# Power_Supply.net
KiCad netlist of a schematic drawn in Altium Designer
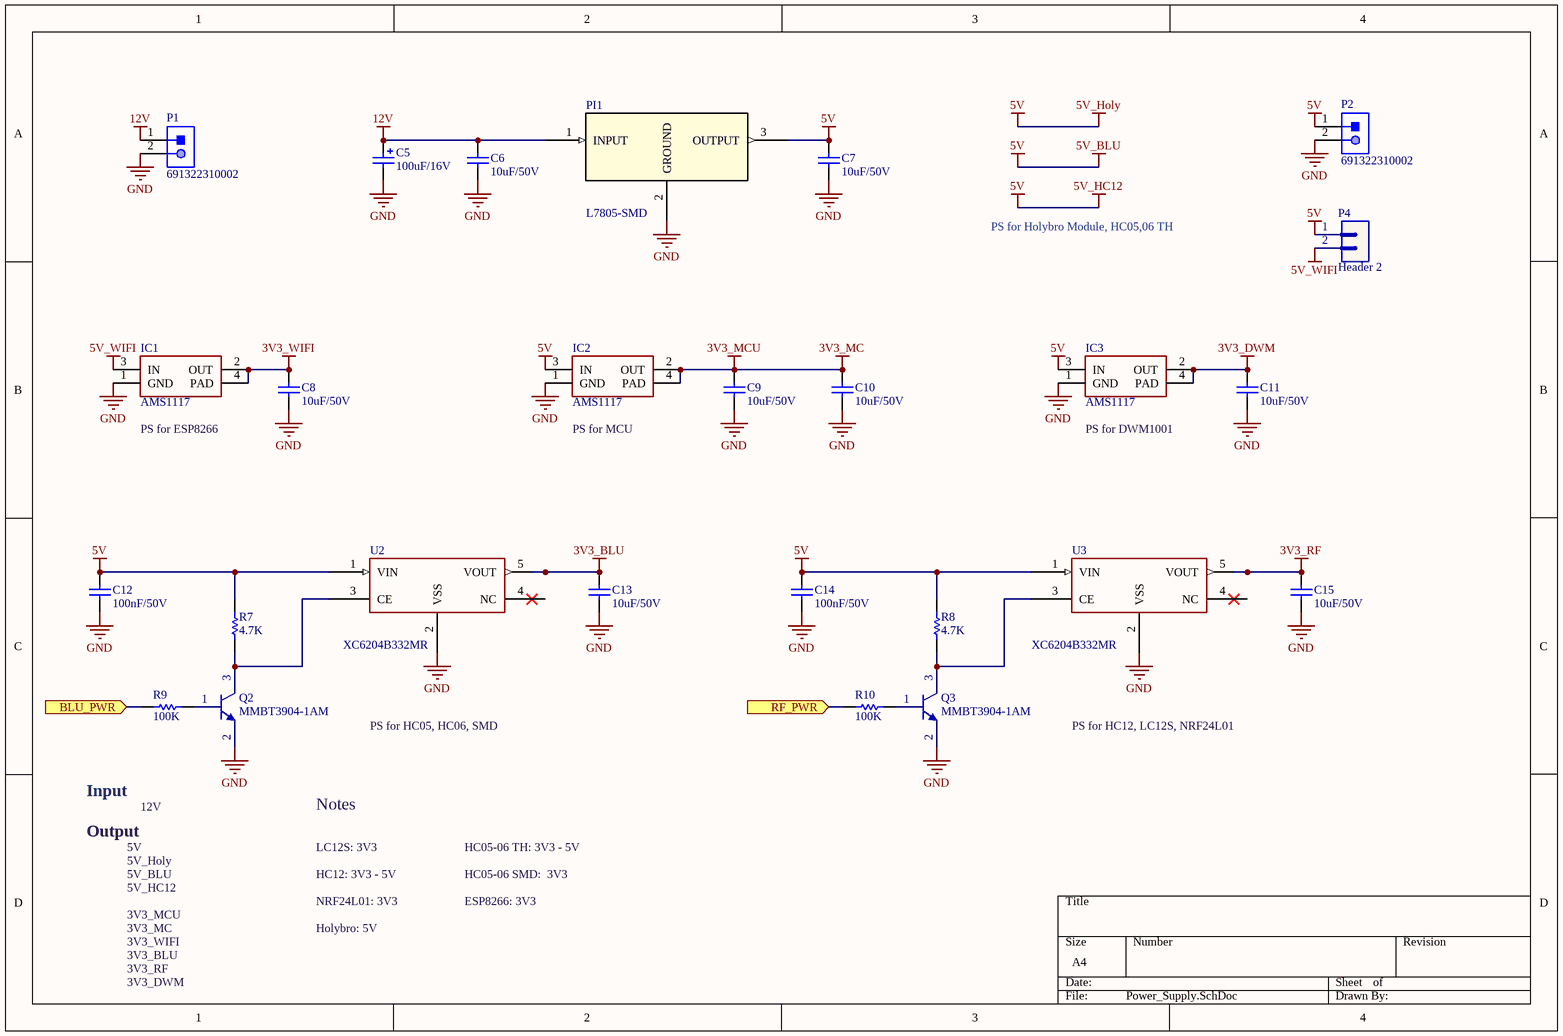
[diagram p0: Power_Supply.SchDoc]

(export (version "E")
  (design (tool "Eeschema 10.0.6"))
  (components
    (comp (ref "C5")
      (value "100uF/16V")
      (footprint "CAP-SM-AL-SIZE-D-D6L6")
      (description "CAP ALUM 100UF 20% 16V SMD")
      (fields
        (field (name "MANUFACTURER") "Nichicon")
        (field (name "MANUFACTURER PART NUMBER") "UWX1C101MCL1GB")
      )
      (libsource (lib "Capacitor") (part "Cap-Al-100uF-16V-D6L5"))
    )
    (comp (ref "C6")
      (value "10uF/50V")
      (footprint "CAP-SM-0805")
      (description "CAP CER 10UF 50V X5R 0805")
      (fields
        (field (name "MANUFACTURER") "Yageo")
        (field (name "MANUFACTURER PART NUMBER") "CC0805KKX5R9BB106")
      )
      (libsource (lib "Capacitor") (part "Cap-10uF-50V-0805"))
    )
    (comp (ref "C7")
      (value "10uF/50V")
      (footprint "CAP-SM-0805")
      (description "CAP CER 10UF 50V X5R 0805")
      (fields
        (field (name "MANUFACTURER") "Yageo")
        (field (name "MANUFACTURER PART NUMBER") "CC0805KKX5R9BB106")
      )
      (libsource (lib "Capacitor") (part "Cap-10uF-50V-0805"))
    )
    (comp (ref "C8")
      (value "10uF/50V")
      (footprint "CAP-SM-0805")
      (description "CAP CER 10UF 50V X5R 0805")
      (fields
        (field (name "MANUFACTURER") "Yageo")
        (field (name "MANUFACTURER PART NUMBER") "CC0805KKX5R9BB106")
      )
      (libsource (lib "Capacitor") (part "Cap-10uF-50V-0805"))
    )
    (comp (ref "C9")
      (value "10uF/50V")
      (footprint "CAP-SM-0805")
      (description "CAP CER 10UF 50V X5R 0805")
      (fields
        (field (name "MANUFACTURER") "Yageo")
        (field (name "MANUFACTURER PART NUMBER") "CC0805KKX5R9BB106")
      )
      (libsource (lib "Capacitor") (part "Cap-10uF-50V-0805"))
    )
    (comp (ref "C10")
      (value "10uF/50V")
      (footprint "CAP-SM-0805")
      (description "CAP CER 10UF 50V X5R 0805")
      (fields
        (field (name "MANUFACTURER") "Yageo")
        (field (name "MANUFACTURER PART NUMBER") "CC0805KKX5R9BB106")
      )
      (libsource (lib "Capacitor") (part "Cap-10uF-50V-0805"))
    )
    (comp (ref "C11")
      (value "10uF/50V")
      (footprint "CAP-SM-0805")
      (description "CAP CER 10UF 50V X5R 0805")
      (fields
        (field (name "MANUFACTURER") "Yageo")
        (field (name "MANUFACTURER PART NUMBER") "CC0805KKX5R9BB106")
      )
      (libsource (lib "Capacitor") (part "Cap-10uF-50V-0805"))
    )
    (comp (ref "C12")
      (value "100nF/50V")
      (footprint "CAP-SM-0805")
      (description "CAP CER 0.1UF 50V Y5V 0805")
      (fields
        (field (name "MANUFACTURER") "Samsung Electro-Mechanics")
        (field (name "MANUFACTURER PART NUMBER") "CL21F104ZBCNNNC")
      )
      (libsource (lib "Capacitor") (part "Cap-100nF-50V-0805"))
    )
    (comp (ref "C13")
      (value "10uF/50V")
      (footprint "CAP-SM-0805")
      (description "CAP CER 10UF 50V X5R 0805")
      (fields
        (field (name "MANUFACTURER") "Yageo")
        (field (name "MANUFACTURER PART NUMBER") "CC0805KKX5R9BB106")
      )
      (libsource (lib "Capacitor") (part "Cap-10uF-50V-0805"))
    )
    (comp (ref "C14")
      (value "100nF/50V")
      (footprint "CAP-SM-0805")
      (description "CAP CER 0.1UF 50V Y5V 0805")
      (fields
        (field (name "MANUFACTURER") "Samsung Electro-Mechanics")
        (field (name "MANUFACTURER PART NUMBER") "CL21F104ZBCNNNC")
      )
      (libsource (lib "Capacitor") (part "Cap-100nF-50V-0805"))
    )
    (comp (ref "C15")
      (value "10uF/50V")
      (footprint "CAP-SM-0805")
      (description "CAP CER 10UF 50V X5R 0805")
      (fields
        (field (name "MANUFACTURER") "Yageo")
        (field (name "MANUFACTURER PART NUMBER") "CC0805KKX5R9BB106")
      )
      (libsource (lib "Capacitor") (part "Cap-10uF-50V-0805"))
    )
    (comp (ref "IC1")
      (value "AMS1117")
      (footprint "SOT223")
      (description "Available in 1.8V, 2.5V, 2.85V, 3.3V, 5V, and  Adjustable Versions")
      (libsource (lib "PI") (part "AMS1117"))
    )
    (comp (ref "IC2")
      (value "AMS1117")
      (footprint "SOT223")
      (description "Available in 1.8V, 2.5V, 2.85V, 3.3V, 5V, and  Adjustable Versions")
      (libsource (lib "PI") (part "AMS1117"))
    )
    (comp (ref "IC3")
      (value "AMS1117")
      (footprint "SOT223")
      (description "Available in 1.8V, 2.5V, 2.85V, 3.3V, 5V, and  Adjustable Versions")
      (libsource (lib "PI") (part "AMS1117"))
    )
    (comp (ref "P1")
      (value "691322310002")
      (footprint "691322310002")
      (description "WR-TBL Serie 322 Horizontal PCB Header, Pluggable, pitch 3.81mm, 2p")
      (fields (field (name "PUBLISHER") "Wurth Elektronik"))
      (libsource (lib "Domino_5mm_691101710002_Altium_WR-TBL_rev19a") (part "691322310002"))
    )
    (comp (ref "P2")
      (value "691322310002")
      (footprint "691322310002")
      (description "WR-TBL Serie 322 Horizontal PCB Header, Pluggable, pitch 3.81mm, 2p")
      (fields (field (name "PUBLISHER") "Wurth Elektronik"))
      (libsource (lib "Domino_5mm_691101710002_Altium_WR-TBL_rev19a") (part "691322310002"))
    )
    (comp (ref "P4")
      (value "Header 2")
      (footprint "JP2")
      (description "Header, 2-Pin")
      (fields (field (name "PUBLISHER") "Altium Limited"))
      (libsource (lib "Header-connector") (part "Header 2"))
    )
    (comp (ref "PI1")
      (value "L7805-SMD")
      (footprint "D2PAK_STM")
      (description "No Description Available")
      (fields
        (field (name "MANUFACTURER_PART_NUMBER") "L7805CD2T-TR")
        (field (name "COPYRIGHT") "Copyright (C) 2018 Accelerated Designs. All rights reserved")
      )
      (libsource (lib "L7805") (part "L7805CD2T-TR"))
    )
    (comp (ref "Q2")
      (value "MMBT3904-1AM")
      (footprint "SOT23_NEX")
      (libsource (lib "BJT") (part "MMBT3904-1AM"))
    )
    (comp (ref "Q3")
      (value "MMBT3904-1AM")
      (footprint "SOT23_NEX")
      (libsource (lib "BJT") (part "MMBT3904-1AM"))
    )
    (comp (ref "R7")
      (value "4.7K")
      (footprint "Resistor:RES-SM-0805")
      (description "RES SMD 4.7K OHM 5% 1/8W 0805")
      (fields
        (field (name "MANUFACTURER") "Yageo")
        (field (name "MANUFACTURER PART NUMBER") "RC0805JR-074K7L")
      )
      (libsource (lib "Resistor") (part "Res-4.7K-0805"))
    )
    (comp (ref "R8")
      (value "4.7K")
      (footprint "Resistor:RES-SM-0805")
      (description "RES SMD 4.7K OHM 5% 1/8W 0805")
      (fields
        (field (name "MANUFACTURER") "Yageo")
        (field (name "MANUFACTURER PART NUMBER") "RC0805JR-074K7L")
      )
      (libsource (lib "Resistor") (part "Res-4.7K-0805"))
    )
    (comp (ref "R9")
      (value "100K")
      (footprint "Resistor:RES-SM-0805")
      (description "RES 0 OHM JUMPER 0805")
      (fields
        (field (name "MANUFACTURER") "Vishay Dale")
        (field (name "MANUFACTURER PART NUMBER") "WSL080500000ZEA9")
      )
      (libsource (lib "Resistor") (part "Res-100K-0805"))
    )
    (comp (ref "R10")
      (value "100K")
      (footprint "Resistor:RES-SM-0805")
      (description "RES 0 OHM JUMPER 0805")
      (fields
        (field (name "MANUFACTURER") "Vishay Dale")
        (field (name "MANUFACTURER PART NUMBER") "WSL080500000ZEA9")
      )
      (libsource (lib "Resistor") (part "Res-100K-0805"))
    )
    (comp (ref "U2")
      (value "XC6204B332MR")
      (footprint "XC6204/05_SOT-00")
      (fields (field (name "COPYRIGHT") "Copyright (C) 2018 Accelerated Designs. All rights reserved"))
      (libsource (lib "PI") (part "XC6204B332MR"))
    )
    (comp (ref "U3")
      (value "XC6204B332MR")
      (footprint "XC6204/05_SOT-00")
      (fields (field (name "COPYRIGHT") "Copyright (C) 2018 Accelerated Designs. All rights reserved"))
      (libsource (lib "PI") (part "XC6204B332MR"))
    )
  )
  (nets
    (net (code "1") (name "/BLU_PWR") (class "Default")
      (node (ref "R9") (pin "1") (pinfunction "1_1") (pintype "passive"))
    )
    (net (code "18") (name "/RF_PWR") (class "Default")
      (node (ref "R10") (pin "1") (pinfunction "1_1") (pintype "passive"))
    )
    (net (code "19") (name "3V3_BLU") (class "Default")
      (node (ref "C13") (pin "2") (pinfunction "2_2") (pintype "passive"))
      (node (ref "U2") (pin "5") (pinfunction "VOUT_5") (pintype "output"))
    )
    (net (code "20") (name "3V3_DWM") (class "Default")
      (node (ref "C11") (pin "2") (pinfunction "2_2") (pintype "passive"))
      (node (ref "IC3") (pin "2") (pinfunction "OUT_2") (pintype "passive"))
      (node (ref "IC3") (pin "4") (pinfunction "PAD_4") (pintype "passive"))
    )
    (net (code "21") (name "3V3_MC") (class "Default")
      (node (ref "C10") (pin "2") (pinfunction "2_2") (pintype "passive"))
      (node (ref "C9") (pin "2") (pinfunction "2_2") (pintype "passive"))
      (node (ref "IC2") (pin "2") (pinfunction "OUT_2") (pintype "passive"))
      (node (ref "IC2") (pin "4") (pinfunction "PAD_4") (pintype "passive"))
    )
    (net (code "22") (name "3V3_RF") (class "Default")
      (node (ref "C15") (pin "2") (pinfunction "2_2") (pintype "passive"))
      (node (ref "U3") (pin "5") (pinfunction "VOUT_5") (pintype "output"))
    )
    (net (code "23") (name "3V3_WIFI") (class "Default")
      (node (ref "C8") (pin "2") (pinfunction "2_2") (pintype "passive"))
      (node (ref "IC1") (pin "2") (pinfunction "OUT_2") (pintype "passive"))
      (node (ref "IC1") (pin "4") (pinfunction "PAD_4") (pintype "passive"))
    )
    (net (code "24") (name "5V") (class "Default")
      (node (ref "C12") (pin "2") (pinfunction "2_2") (pintype "passive"))
      (node (ref "C14") (pin "2") (pinfunction "2_2") (pintype "passive"))
      (node (ref "C7") (pin "2") (pinfunction "2_2") (pintype "passive"))
      (node (ref "IC2") (pin "3") (pinfunction "IN_3") (pintype "passive"))
      (node (ref "IC3") (pin "3") (pinfunction "IN_3") (pintype "passive"))
      (node (ref "P2") (pin "1") (pinfunction "1_1") (pintype "passive"))
      (node (ref "P4") (pin "1") (pinfunction "1_1") (pintype "passive"))
      (node (ref "PI1") (pin "3") (pinfunction "OUTPUT_3") (pintype "output"))
      (node (ref "R7") (pin "2") (pinfunction "2_2") (pintype "passive"))
      (node (ref "R8") (pin "2") (pinfunction "2_2") (pintype "passive"))
      (node (ref "U2") (pin "1") (pinfunction "VIN_1") (pintype "input"))
      (node (ref "U3") (pin "1") (pinfunction "VIN_1") (pintype "input"))
    )
    (net (code "25") (name "5V_WIFI") (class "Default")
      (node (ref "IC1") (pin "3") (pinfunction "IN_3") (pintype "passive"))
      (node (ref "P4") (pin "2") (pinfunction "2_2") (pintype "passive"))
    )
    (net (code "26") (name "12V") (class "Default")
      (node (ref "C5") (pin "1") (pinfunction "1_1") (pintype "passive"))
      (node (ref "C6") (pin "2") (pinfunction "2_2") (pintype "passive"))
      (node (ref "P1") (pin "1") (pinfunction "1_1") (pintype "passive"))
      (node (ref "PI1") (pin "1") (pinfunction "INPUT_1") (pintype "input"))
    )
    (net (code "27") (name "GND") (class "Default")
      (node (ref "C10") (pin "1") (pinfunction "1_1") (pintype "passive"))
      (node (ref "C11") (pin "1") (pinfunction "1_1") (pintype "passive"))
      (node (ref "C12") (pin "1") (pinfunction "1_1") (pintype "passive"))
      (node (ref "C13") (pin "1") (pinfunction "1_1") (pintype "passive"))
      (node (ref "C14") (pin "1") (pinfunction "1_1") (pintype "passive"))
      (node (ref "C15") (pin "1") (pinfunction "1_1") (pintype "passive"))
      (node (ref "C5") (pin "2") (pinfunction "2_2") (pintype "passive"))
      (node (ref "C6") (pin "1") (pinfunction "1_1") (pintype "passive"))
      (node (ref "C7") (pin "1") (pinfunction "1_1") (pintype "passive"))
      (node (ref "C8") (pin "1") (pinfunction "1_1") (pintype "passive"))
      (node (ref "C9") (pin "1") (pinfunction "1_1") (pintype "passive"))
      (node (ref "IC1") (pin "1") (pinfunction "GND_1") (pintype "passive"))
      (node (ref "IC2") (pin "1") (pinfunction "GND_1") (pintype "passive"))
      (node (ref "IC3") (pin "1") (pinfunction "GND_1") (pintype "passive"))
      (node (ref "P1") (pin "2") (pinfunction "2_2") (pintype "passive"))
      (node (ref "P2") (pin "2") (pinfunction "2_2") (pintype "passive"))
      (node (ref "PI1") (pin "2") (pinfunction "GROUND_2") (pintype "passive"))
      (node (ref "Q2") (pin "2") (pinfunction "E_2") (pintype "passive"))
      (node (ref "Q3") (pin "2") (pinfunction "E_2") (pintype "passive"))
      (node (ref "U2") (pin "2") (pinfunction "VSS_2") (pintype "passive"))
      (node (ref "U3") (pin "2") (pinfunction "VSS_2") (pintype "passive"))
    )
    (net (code "28") (name "Net-(Q2-B)") (class "Default")
      (node (ref "Q2") (pin "1") (pinfunction "B_1") (pintype "passive"))
      (node (ref "R9") (pin "2") (pinfunction "2_2") (pintype "passive"))
    )
    (net (code "29") (name "Net-(Q2-C)") (class "Default")
      (node (ref "Q2") (pin "3") (pinfunction "C_3") (pintype "passive"))
      (node (ref "R7") (pin "1") (pinfunction "1_1") (pintype "passive"))
      (node (ref "U2") (pin "3") (pinfunction "CE_3") (pintype "passive"))
    )
    (net (code "30") (name "Net-(Q3-B)") (class "Default")
      (node (ref "Q3") (pin "1") (pinfunction "B_1") (pintype "passive"))
      (node (ref "R10") (pin "2") (pinfunction "2_2") (pintype "passive"))
    )
    (net (code "31") (name "Net-(Q3-C)") (class "Default")
      (node (ref "Q3") (pin "3") (pinfunction "C_3") (pintype "passive"))
      (node (ref "R8") (pin "1") (pinfunction "1_1") (pintype "passive"))
      (node (ref "U3") (pin "3") (pinfunction "CE_3") (pintype "passive"))
    )
    (net (code "32") (name "unconnected-(U2-NC-Pad4)") (class "Default")
      (node (ref "U2") (pin "4") (pinfunction "NC_4") (pintype "passive"))
    )
    (net (code "33") (name "unconnected-(U3-NC-Pad4)") (class "Default")
      (node (ref "U3") (pin "4") (pinfunction "NC_4") (pintype "passive"))
    )
  )
)
